# audio-ext.net
KiCad netlist of a schematic drawn in EAGLE
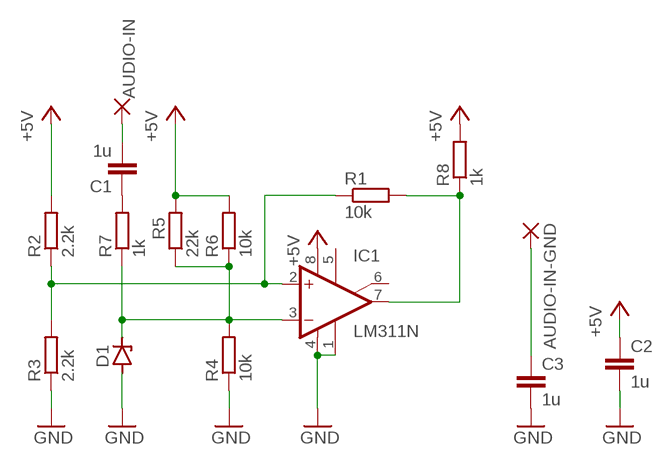
[diagram p0: schematic, sheet 1]

(export (version "E")
  (design (tool "Eeschema 10.0.6"))
  (components
    (comp (ref "AUDIO-IN")
      (value "WIREPAD1,6/0,8")
      (footprint "eagle-import:1,6_0,8")
      (libsource (lib "eagle-import") (part "WIREPAD1,6/0,8"))
    )
    (comp (ref "AUDIO-IN-GND")
      (value "WIREPAD1,6/0,8")
      (footprint "eagle-import:1,6_0,8")
      (libsource (lib "eagle-import") (part "WIREPAD1,6/0,8"))
    )
    (comp (ref "C1")
      (value "1u")
      (footprint "eagle-import:C0805")
      (libsource (lib "eagle-import") (part "C-EUC0805"))
    )
    (comp (ref "C2")
      (value "1u")
      (footprint "eagle-import:C0805")
      (libsource (lib "eagle-import") (part "C-EUC0805"))
    )
    (comp (ref "C3")
      (value "1u")
      (footprint "eagle-import:C0805")
      (libsource (lib "eagle-import") (part "C-EUC0805"))
    )
    (comp (ref "D1")
      (value "ZENER-DIODESOT23")
      (footprint "eagle-import:SOT23")
      (libsource (lib "eagle-import") (part "ZENER-DIODESOT23"))
    )
    (comp (ref "IC1")
      (value "LM311N")
      (footprint "eagle-import:DIL08")
      (libsource (lib "eagle-import") (part "LM311N"))
    )
    (comp (ref "R1")
      (value "10k")
      (footprint "eagle-import:R0805")
      (libsource (lib "eagle-import") (part "R-EU_R0805"))
    )
    (comp (ref "R2")
      (value "2.2k")
      (footprint "eagle-import:R0805")
      (libsource (lib "eagle-import") (part "R-EU_R0805"))
    )
    (comp (ref "R3")
      (value "2.2k")
      (footprint "eagle-import:R0805")
      (libsource (lib "eagle-import") (part "R-EU_R0805"))
    )
    (comp (ref "R4")
      (value "10k")
      (footprint "eagle-import:R0805")
      (libsource (lib "eagle-import") (part "R-EU_R0805"))
    )
    (comp (ref "R5")
      (value "22k")
      (footprint "eagle-import:R0805")
      (libsource (lib "eagle-import") (part "R-EU_R0805"))
    )
    (comp (ref "R6")
      (value "10k")
      (footprint "eagle-import:R0805")
      (libsource (lib "eagle-import") (part "R-EU_R0805"))
    )
    (comp (ref "R7")
      (value "1k")
      (footprint "eagle-import:R0805")
      (libsource (lib "eagle-import") (part "R-EU_R0805"))
    )
    (comp (ref "R8")
      (value "1k")
      (footprint "eagle-import:R0805")
      (libsource (lib "eagle-import") (part "R-EU_R0805"))
    )
  )
  (nets
    (net (code "1") (name "+5V") (class "Default")
      (node (ref "C2") (pin "1") (pinfunction "1_1") (pintype "passive"))
      (node (ref "IC1") (pin "8") (pinfunction "V+_8") (pintype "power_in"))
      (node (ref "R2") (pin "2") (pinfunction "2_2") (pintype "passive"))
      (node (ref "R5") (pin "2") (pinfunction "2_2") (pintype "passive"))
      (node (ref "R6") (pin "2") (pinfunction "2_2") (pintype "passive"))
      (node (ref "R8") (pin "2") (pinfunction "2_2") (pintype "passive"))
    )
    (net (code "2") (name "GND") (class "Default")
      (node (ref "C2") (pin "2") (pinfunction "2_2") (pintype "passive"))
      (node (ref "C3") (pin "2") (pinfunction "2_2") (pintype "passive"))
      (node (ref "D1") (pin "1") (pinfunction "A_1") (pintype "passive"))
      (node (ref "IC1") (pin "1") (pinfunction "GND_1") (pintype "passive"))
      (node (ref "IC1") (pin "4") (pinfunction "V-_4") (pintype "power_in"))
      (node (ref "R3") (pin "1") (pinfunction "1_1") (pintype "passive"))
      (node (ref "R4") (pin "1") (pinfunction "1_1") (pintype "passive"))
    )
    (net (code "3") (name "Net-(AUDIO-IN-GND-P)") (class "Default")
      (node (ref "AUDIO-IN-GND") (pin "1") (pinfunction "P_1") (pintype "passive"))
      (node (ref "C3") (pin "1") (pinfunction "1_1") (pintype "passive"))
    )
    (net (code "4") (name "Net-(AUDIO-IN-P)") (class "Default")
      (node (ref "AUDIO-IN") (pin "1") (pinfunction "P_1") (pintype "passive"))
      (node (ref "C1") (pin "2") (pinfunction "2_2") (pintype "passive"))
    )
    (net (code "5") (name "Net-(C1-Pad1)") (class "Default")
      (node (ref "C1") (pin "1") (pinfunction "1_1") (pintype "passive"))
      (node (ref "R7") (pin "2") (pinfunction "2_2") (pintype "passive"))
    )
    (net (code "6") (name "Net-(D1-C)") (class "Default")
      (node (ref "D1") (pin "3") (pinfunction "C_3") (pintype "passive"))
      (node (ref "IC1") (pin "3") (pinfunction "-IN_3") (pintype "input"))
      (node (ref "R4") (pin "2") (pinfunction "2_2") (pintype "passive"))
      (node (ref "R5") (pin "1") (pinfunction "1_1") (pintype "passive"))
      (node (ref "R6") (pin "1") (pinfunction "1_1") (pintype "passive"))
      (node (ref "R7") (pin "1") (pinfunction "1_1") (pintype "passive"))
    )
    (net (code "7") (name "Net-(IC1-+IN)") (class "Default")
      (node (ref "IC1") (pin "2") (pinfunction "+IN_2") (pintype "input"))
      (node (ref "R1") (pin "1") (pinfunction "1_1") (pintype "passive"))
      (node (ref "R2") (pin "1") (pinfunction "1_1") (pintype "passive"))
      (node (ref "R3") (pin "2") (pinfunction "2_2") (pintype "passive"))
    )
    (net (code "8") (name "Net-(IC1-OUT)") (class "Default")
      (node (ref "IC1") (pin "7") (pinfunction "OUT_7") (pintype "output"))
      (node (ref "R1") (pin "2") (pinfunction "2_2") (pintype "passive"))
      (node (ref "R8") (pin "1") (pinfunction "1_1") (pintype "passive"))
    )
    (net (code "9") (name "unconnected-(IC1-ON-Pad5)") (class "Default")
      (node (ref "IC1") (pin "5") (pinfunction "ON_5") (pintype "passive"))
    )
    (net (code "10") (name "unconnected-(IC1-ON{slash}STR-Pad6)") (class "Default")
      (node (ref "IC1") (pin "6") (pinfunction "ON/STR_6") (pintype "passive"))
    )
  )
)
